# GroundStationOBA.net
KiCad netlist of a schematic drawn in EAGLE
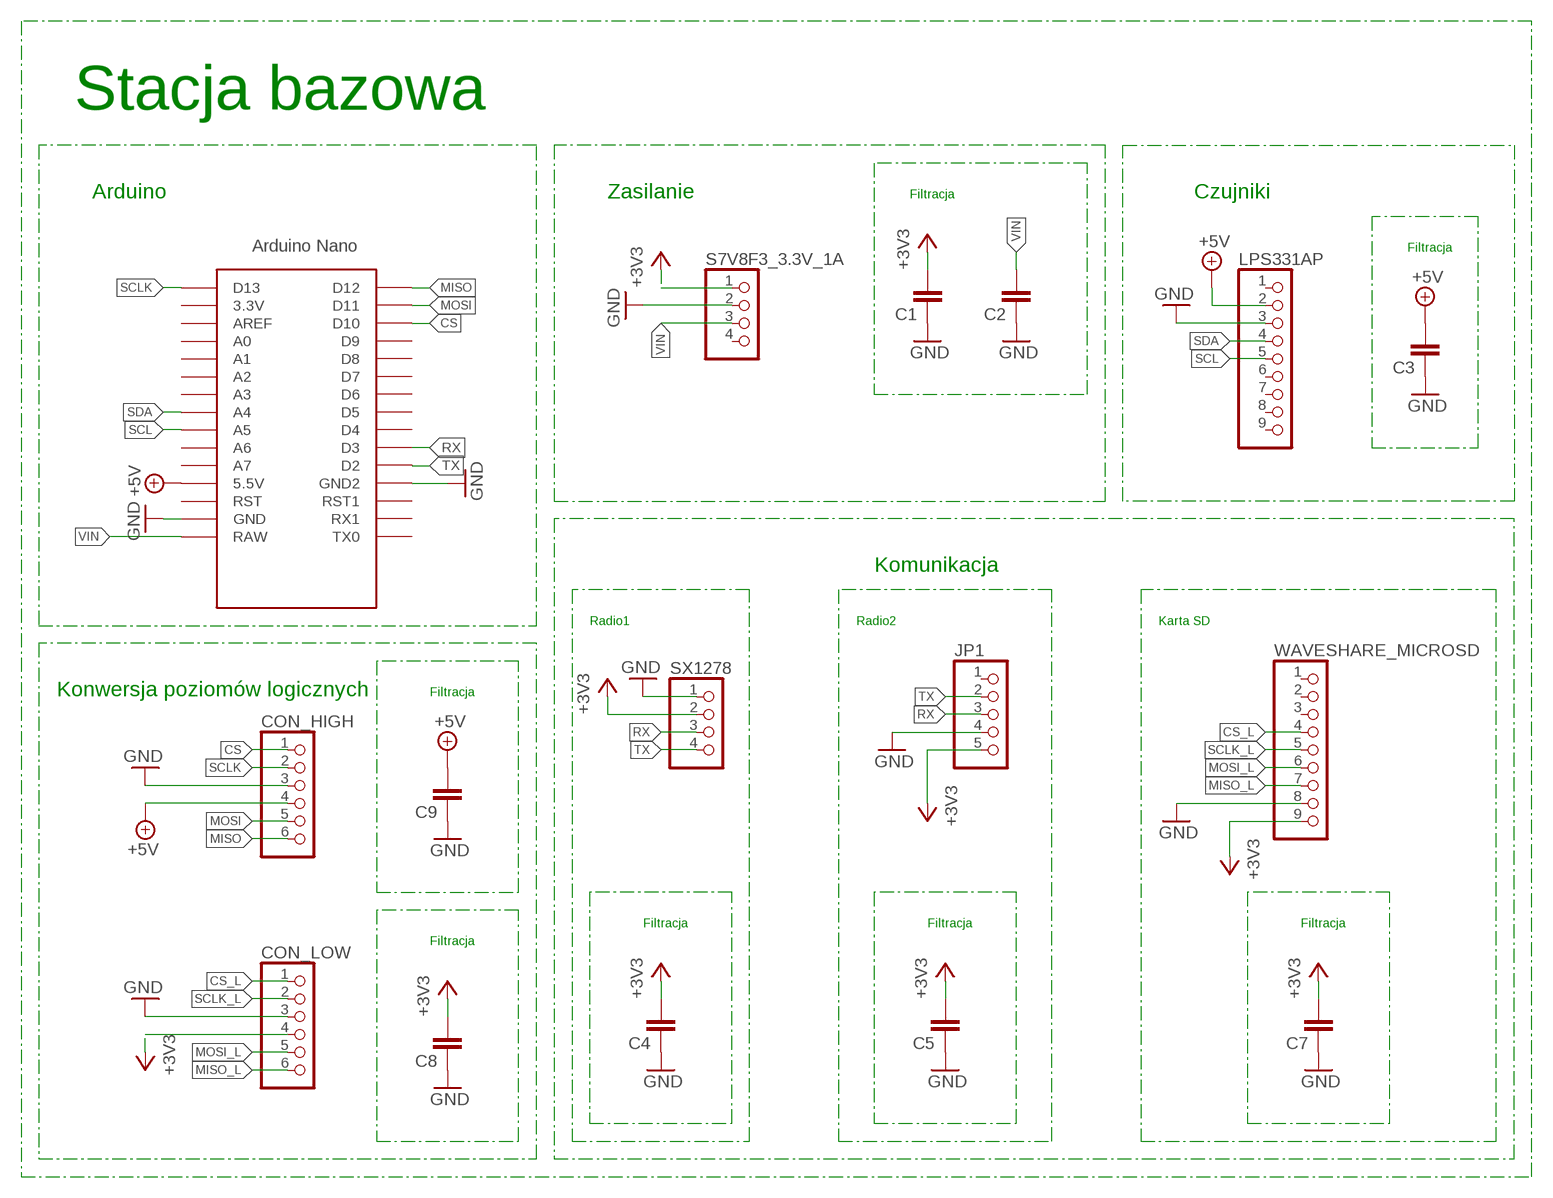
[diagram p0: schematic, sheet 1]

(export (version "E")
  (design (tool "Eeschema 10.0.6"))
  (components
    (comp (ref "C1")
      (value "C-EU050-025X075")
      (footprint "eagle-import:C050-025X075")
      (libsource (lib "eagle-import") (part "C-EU050-025X075"))
    )
    (comp (ref "C2")
      (value "C-EU050-025X075")
      (footprint "eagle-import:C050-025X075")
      (libsource (lib "eagle-import") (part "C-EU050-025X075"))
    )
    (comp (ref "C3")
      (value "C-EU050-025X075")
      (footprint "eagle-import:C050-025X075")
      (libsource (lib "eagle-import") (part "C-EU050-025X075"))
    )
    (comp (ref "C4")
      (value "C-EU050-025X075")
      (footprint "eagle-import:C050-025X075")
      (libsource (lib "eagle-import") (part "C-EU050-025X075"))
    )
    (comp (ref "C5")
      (value "C-EU050-025X075")
      (footprint "eagle-import:C050-025X075")
      (libsource (lib "eagle-import") (part "C-EU050-025X075"))
    )
    (comp (ref "C7")
      (value "C-EU050-025X075")
      (footprint "eagle-import:C050-025X075")
      (libsource (lib "eagle-import") (part "C-EU050-025X075"))
    )
    (comp (ref "C8")
      (value "C-EU050-025X075")
      (footprint "eagle-import:C050-025X075")
      (libsource (lib "eagle-import") (part "C-EU050-025X075"))
    )
    (comp (ref "C9")
      (value "C-EU050-025X075")
      (footprint "eagle-import:C050-025X075")
      (libsource (lib "eagle-import") (part "C-EU050-025X075"))
    )
    (comp (ref "CON_HIGH")
      (value "PINHD-1X6")
      (footprint "eagle-import:1X06")
      (libsource (lib "eagle-import") (part "PINHD-1X6"))
    )
    (comp (ref "CON_LOW")
      (value "PINHD-1X6")
      (footprint "eagle-import:1X06")
      (libsource (lib "eagle-import") (part "PINHD-1X6"))
    )
    (comp (ref "JP1")
      (value "PINHD-1X5")
      (footprint "eagle-import:1X05")
      (libsource (lib "eagle-import") (part "PINHD-1X5"))
    )
    (comp (ref "LPS331AP")
      (value "PINHD-1X9")
      (footprint "eagle-import:1X09")
      (libsource (lib "eagle-import") (part "PINHD-1X9"))
    )
    (comp (ref "S7V8F3_3.3V_1A")
      (value "PINHD-1X4")
      (footprint "eagle-import:1X04")
      (libsource (lib "eagle-import") (part "PINHD-1X4"))
    )
    (comp (ref "SX1278")
      (value "PINHD-1X4")
      (footprint "eagle-import:1X04")
      (libsource (lib "eagle-import") (part "PINHD-1X4"))
    )
    (comp (ref "U$1")
      (value "NANO")
      (footprint "eagle-import:NANO")
      (libsource (lib "eagle-import") (part "NANO"))
    )
    (comp (ref "WAVESHARE_MICROSD")
      (value "PINHD-1X9")
      (footprint "eagle-import:1X09")
      (libsource (lib "eagle-import") (part "PINHD-1X9"))
    )
  )
  (nets
    (net (code "1") (name "+3V3") (class "Default")
      (node (ref "C1") (pin "2") (pinfunction "2_2") (pintype "passive"))
      (node (ref "C4") (pin "2") (pinfunction "2_2") (pintype "passive"))
      (node (ref "C5") (pin "2") (pinfunction "2_2") (pintype "passive"))
      (node (ref "C7") (pin "2") (pinfunction "2_2") (pintype "passive"))
      (node (ref "C8") (pin "2") (pinfunction "2_2") (pintype "passive"))
      (node (ref "CON_LOW") (pin "4") (pinfunction "4_4") (pintype "passive"))
      (node (ref "JP1") (pin "5") (pinfunction "5_5") (pintype "passive"))
      (node (ref "S7V8F3_3.3V_1A") (pin "1") (pinfunction "1_1") (pintype "passive"))
      (node (ref "SX1278") (pin "2") (pinfunction "2_2") (pintype "passive"))
      (node (ref "WAVESHARE_MICROSD") (pin "9") (pinfunction "9_9") (pintype "passive"))
    )
    (net (code "2") (name "+5V") (class "Default")
      (node (ref "C3") (pin "2") (pinfunction "2_2") (pintype "passive"))
      (node (ref "C9") (pin "2") (pinfunction "2_2") (pintype "passive"))
      (node (ref "CON_HIGH") (pin "4") (pinfunction "4_4") (pintype "passive"))
      (node (ref "LPS331AP") (pin "2") (pinfunction "2_2") (pintype "passive"))
      (node (ref "U$1") (pin "5V") (pinfunction "5.5V_5V") (pintype "bidirectional"))
    )
    (net (code "3") (name "CS") (class "Default")
      (node (ref "CON_HIGH") (pin "1") (pinfunction "1_1") (pintype "passive"))
      (node (ref "U$1") (pin "D10") (pinfunction "D10_D10") (pintype "bidirectional"))
    )
    (net (code "4") (name "CS_L") (class "Default")
      (node (ref "CON_LOW") (pin "1") (pinfunction "1_1") (pintype "passive"))
      (node (ref "WAVESHARE_MICROSD") (pin "4") (pinfunction "4_4") (pintype "passive"))
    )
    (net (code "5") (name "GND") (class "Default")
      (node (ref "C1") (pin "1") (pinfunction "1_1") (pintype "passive"))
      (node (ref "C2") (pin "1") (pinfunction "1_1") (pintype "passive"))
      (node (ref "C3") (pin "1") (pinfunction "1_1") (pintype "passive"))
      (node (ref "C4") (pin "1") (pinfunction "1_1") (pintype "passive"))
      (node (ref "C5") (pin "1") (pinfunction "1_1") (pintype "passive"))
      (node (ref "C7") (pin "1") (pinfunction "1_1") (pintype "passive"))
      (node (ref "C8") (pin "1") (pinfunction "1_1") (pintype "passive"))
      (node (ref "C9") (pin "1") (pinfunction "1_1") (pintype "passive"))
      (node (ref "CON_HIGH") (pin "3") (pinfunction "3_3") (pintype "passive"))
      (node (ref "CON_LOW") (pin "3") (pinfunction "3_3") (pintype "passive"))
      (node (ref "JP1") (pin "4") (pinfunction "4_4") (pintype "passive"))
      (node (ref "LPS331AP") (pin "3") (pinfunction "3_3") (pintype "passive"))
      (node (ref "S7V8F3_3.3V_1A") (pin "2") (pinfunction "2_2") (pintype "passive"))
      (node (ref "SX1278") (pin "1") (pinfunction "1_1") (pintype "passive"))
      (node (ref "U$1") (pin "GND") (pinfunction "GND_GND") (pintype "bidirectional"))
      (node (ref "U$1") (pin "GND1") (pinfunction "GND2_GND1") (pintype "bidirectional"))
      (node (ref "WAVESHARE_MICROSD") (pin "8") (pinfunction "8_8") (pintype "passive"))
    )
    (net (code "6") (name "MISO") (class "Default")
      (node (ref "CON_HIGH") (pin "6") (pinfunction "6_6") (pintype "passive"))
      (node (ref "U$1") (pin "D12") (pinfunction "D12_D12") (pintype "bidirectional"))
    )
    (net (code "7") (name "MISO_L") (class "Default")
      (node (ref "CON_LOW") (pin "6") (pinfunction "6_6") (pintype "passive"))
      (node (ref "WAVESHARE_MICROSD") (pin "7") (pinfunction "7_7") (pintype "passive"))
    )
    (net (code "8") (name "MOSI") (class "Default")
      (node (ref "CON_HIGH") (pin "5") (pinfunction "5_5") (pintype "passive"))
      (node (ref "U$1") (pin "D11") (pinfunction "D11_D11") (pintype "bidirectional"))
    )
    (net (code "9") (name "MOSI_L") (class "Default")
      (node (ref "CON_LOW") (pin "5") (pinfunction "5_5") (pintype "passive"))
      (node (ref "WAVESHARE_MICROSD") (pin "6") (pinfunction "6_6") (pintype "passive"))
    )
    (net (code "10") (name "RX") (class "Default")
      (node (ref "JP1") (pin "3") (pinfunction "3_3") (pintype "passive"))
      (node (ref "SX1278") (pin "3") (pinfunction "3_3") (pintype "passive"))
      (node (ref "U$1") (pin "D3") (pinfunction "D3_D3") (pintype "bidirectional"))
    )
    (net (code "11") (name "SCL") (class "Default")
      (node (ref "LPS331AP") (pin "5") (pinfunction "5_5") (pintype "passive"))
      (node (ref "U$1") (pin "A5") (pinfunction "A5_A5") (pintype "bidirectional"))
    )
    (net (code "12") (name "SCLK") (class "Default")
      (node (ref "CON_HIGH") (pin "2") (pinfunction "2_2") (pintype "passive"))
      (node (ref "U$1") (pin "D13") (pinfunction "D13_D13") (pintype "bidirectional"))
    )
    (net (code "13") (name "SCLK_L") (class "Default")
      (node (ref "CON_LOW") (pin "2") (pinfunction "2_2") (pintype "passive"))
      (node (ref "WAVESHARE_MICROSD") (pin "5") (pinfunction "5_5") (pintype "passive"))
    )
    (net (code "14") (name "SDA") (class "Default")
      (node (ref "LPS331AP") (pin "4") (pinfunction "4_4") (pintype "passive"))
      (node (ref "U$1") (pin "A4") (pinfunction "A4_A4") (pintype "bidirectional"))
    )
    (net (code "15") (name "TX") (class "Default")
      (node (ref "JP1") (pin "2") (pinfunction "2_2") (pintype "passive"))
      (node (ref "SX1278") (pin "4") (pinfunction "4_4") (pintype "passive"))
      (node (ref "U$1") (pin "D2") (pinfunction "D2_D2") (pintype "bidirectional"))
    )
    (net (code "16") (name "VIN") (class "Default")
      (node (ref "C2") (pin "2") (pinfunction "2_2") (pintype "passive"))
      (node (ref "S7V8F3_3.3V_1A") (pin "3") (pinfunction "3_3") (pintype "passive"))
      (node (ref "U$1") (pin "RAW") (pinfunction "RAW_RAW") (pintype "bidirectional"))
    )
    (net (code "17") (name "unconnected-(JP1-Pad1)") (class "Default")
      (node (ref "JP1") (pin "1") (pinfunction "1_1") (pintype "passive"))
    )
    (net (code "18") (name "unconnected-(LPS331AP-Pad1)") (class "Default")
      (node (ref "LPS331AP") (pin "1") (pinfunction "1_1") (pintype "passive"))
    )
    (net (code "19") (name "unconnected-(LPS331AP-Pad6)") (class "Default")
      (node (ref "LPS331AP") (pin "6") (pinfunction "6_6") (pintype "passive"))
    )
    (net (code "20") (name "unconnected-(LPS331AP-Pad7)") (class "Default")
      (node (ref "LPS331AP") (pin "7") (pinfunction "7_7") (pintype "passive"))
    )
    (net (code "21") (name "unconnected-(LPS331AP-Pad8)") (class "Default")
      (node (ref "LPS331AP") (pin "8") (pinfunction "8_8") (pintype "passive"))
    )
    (net (code "22") (name "unconnected-(LPS331AP-Pad9)") (class "Default")
      (node (ref "LPS331AP") (pin "9") (pinfunction "9_9") (pintype "passive"))
    )
    (net (code "23") (name "unconnected-(S7V8F3_3.3V_1A-Pad4)") (class "Default")
      (node (ref "S7V8F3_3.3V_1A") (pin "4") (pinfunction "4_4") (pintype "passive"))
    )
    (net (code "24") (name "unconnected-(U$1-Pad3.3V)") (class "Default")
      (node (ref "U$1") (pin "3.3V") (pinfunction "3.3V_3.3V") (pintype "bidirectional"))
    )
    (net (code "25") (name "unconnected-(U$1-PadA0)") (class "Default")
      (node (ref "U$1") (pin "A0") (pinfunction "A0_A0") (pintype "bidirectional"))
    )
    (net (code "26") (name "unconnected-(U$1-PadA1)") (class "Default")
      (node (ref "U$1") (pin "A1") (pinfunction "A1_A1") (pintype "bidirectional"))
    )
    (net (code "27") (name "unconnected-(U$1-PadA2)") (class "Default")
      (node (ref "U$1") (pin "A2") (pinfunction "A2_A2") (pintype "bidirectional"))
    )
    (net (code "28") (name "unconnected-(U$1-PadA3)") (class "Default")
      (node (ref "U$1") (pin "A3") (pinfunction "A3_A3") (pintype "bidirectional"))
    )
    (net (code "29") (name "unconnected-(U$1-PadA6)") (class "Default")
      (node (ref "U$1") (pin "A6") (pinfunction "A6_A6") (pintype "bidirectional"))
    )
    (net (code "30") (name "unconnected-(U$1-PadA7)") (class "Default")
      (node (ref "U$1") (pin "A7") (pinfunction "A7_A7") (pintype "bidirectional"))
    )
    (net (code "31") (name "unconnected-(U$1-PadAREF)") (class "Default")
      (node (ref "U$1") (pin "AREF") (pinfunction "AREF_AREF") (pintype "bidirectional"))
    )
    (net (code "32") (name "unconnected-(U$1-PadD4)") (class "Default")
      (node (ref "U$1") (pin "D4") (pinfunction "D4_D4") (pintype "bidirectional"))
    )
    (net (code "33") (name "unconnected-(U$1-PadD5)") (class "Default")
      (node (ref "U$1") (pin "D5") (pinfunction "D5_D5") (pintype "bidirectional"))
    )
    (net (code "34") (name "unconnected-(U$1-PadD6)") (class "Default")
      (node (ref "U$1") (pin "D6") (pinfunction "D6_D6") (pintype "bidirectional"))
    )
    (net (code "35") (name "unconnected-(U$1-PadD7)") (class "Default")
      (node (ref "U$1") (pin "D7") (pinfunction "D7_D7") (pintype "bidirectional"))
    )
    (net (code "36") (name "unconnected-(U$1-PadD8)") (class "Default")
      (node (ref "U$1") (pin "D8") (pinfunction "D8_D8") (pintype "bidirectional"))
    )
    (net (code "37") (name "unconnected-(U$1-PadD9)") (class "Default")
      (node (ref "U$1") (pin "D9") (pinfunction "D9_D9") (pintype "bidirectional"))
    )
    (net (code "38") (name "unconnected-(U$1-PadICSP1)") (class "Default")
      (node (ref "U$1") (pin "ICSP1") (pinfunction "ICSP1_ICSP1") (pintype "bidirectional"))
    )
    (net (code "39") (name "unconnected-(U$1-PadICSP2)") (class "Default")
      (node (ref "U$1") (pin "ICSP2") (pinfunction "ICSP2_ICSP2") (pintype "bidirectional"))
    )
    (net (code "40") (name "unconnected-(U$1-PadICSP3)") (class "Default")
      (node (ref "U$1") (pin "ICSP3") (pinfunction "ICSP3_ICSP3") (pintype "bidirectional"))
    )
    (net (code "41") (name "unconnected-(U$1-PadICSP4)") (class "Default")
      (node (ref "U$1") (pin "ICSP4") (pinfunction "ICSP4_ICSP4") (pintype "bidirectional"))
    )
    (net (code "42") (name "unconnected-(U$1-PadICSP5)") (class "Default")
      (node (ref "U$1") (pin "ICSP5") (pinfunction "ICSP5_ICSP5") (pintype "bidirectional"))
    )
    (net (code "43") (name "unconnected-(U$1-PadICSP6)") (class "Default")
      (node (ref "U$1") (pin "ICSP6") (pinfunction "ICSP6_ICSP6") (pintype "bidirectional"))
    )
    (net (code "44") (name "unconnected-(U$1-PadRST)") (class "Default")
      (node (ref "U$1") (pin "RST") (pinfunction "RST_RST") (pintype "bidirectional"))
    )
    (net (code "45") (name "unconnected-(U$1-PadRST1)") (class "Default")
      (node (ref "U$1") (pin "RST1") (pinfunction "RST1_RST1") (pintype "bidirectional"))
    )
    (net (code "46") (name "unconnected-(U$1-PadRX1)") (class "Default")
      (node (ref "U$1") (pin "RX1") (pinfunction "RX1_RX1") (pintype "bidirectional"))
    )
    (net (code "47") (name "unconnected-(U$1-PadTX0)") (class "Default")
      (node (ref "U$1") (pin "TX0") (pinfunction "TX0_TX0") (pintype "bidirectional"))
    )
    (net (code "48") (name "unconnected-(WAVESHARE_MICROSD-Pad1)") (class "Default")
      (node (ref "WAVESHARE_MICROSD") (pin "1") (pinfunction "1_1") (pintype "passive"))
    )
    (net (code "49") (name "unconnected-(WAVESHARE_MICROSD-Pad2)") (class "Default")
      (node (ref "WAVESHARE_MICROSD") (pin "2") (pinfunction "2_2") (pintype "passive"))
    )
    (net (code "50") (name "unconnected-(WAVESHARE_MICROSD-Pad3)") (class "Default")
      (node (ref "WAVESHARE_MICROSD") (pin "3") (pinfunction "3_3") (pintype "passive"))
    )
  )
)
